# eib-64.net
KiCad netlist of a schematic drawn in EAGLE
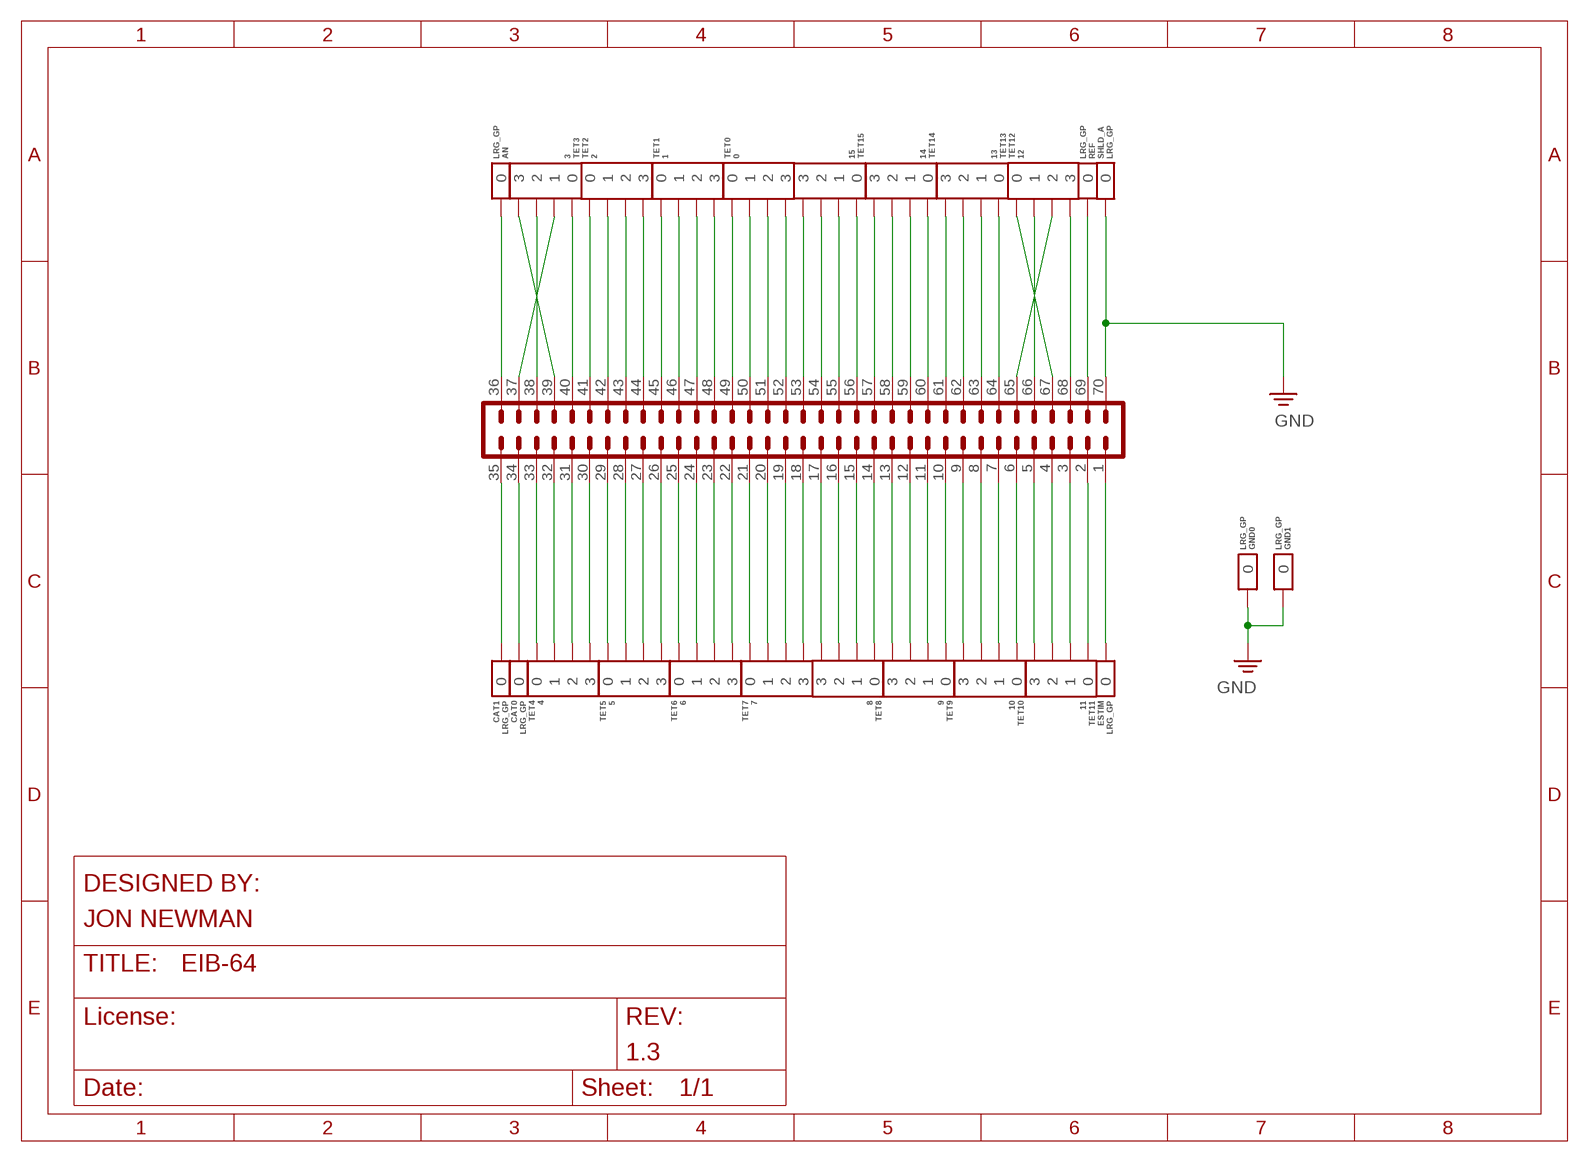
[diagram p0: schematic, sheet 1]

(export (version "E")
  (design (tool "Eeschema 10.0.6"))
  (components
    (comp (ref "AN")
      (value "LRG_GP")
      (footprint "eagle-import:GOLDPIN_0.5ID_0.7OD")
      (libsource (lib "eagle-import") (part "GOLDPIN_0.5ID_0.7OD"))
    )
    (comp (ref "CAT0")
      (value "LRG_GP")
      (footprint "eagle-import:GOLDPIN_0.5ID_0.7OD")
      (libsource (lib "eagle-import") (part "GOLDPIN_0.5ID_0.7OD"))
    )
    (comp (ref "CAT1")
      (value "LRG_GP")
      (footprint "eagle-import:GOLDPIN_0.5ID_0.7OD")
      (libsource (lib "eagle-import") (part "GOLDPIN_0.5ID_0.7OD"))
    )
    (comp (ref "ESTIM")
      (value "LRG_GP")
      (footprint "eagle-import:GOLDPIN_0.5ID_0.7OD")
      (libsource (lib "eagle-import") (part "GOLDPIN_0.5ID_0.7OD"))
    )
    (comp (ref "GND0")
      (value "LRG_GP")
      (footprint "eagle-import:GOLDPIN_0.5ID_0.7OD")
      (libsource (lib "eagle-import") (part "GOLDPIN_0.5ID_0.7OD"))
    )
    (comp (ref "GND1")
      (value "LRG_GP")
      (footprint "eagle-import:GOLDPIN_0.5ID_0.7OD")
      (libsource (lib "eagle-import") (part "GOLDPIN_0.5ID_0.7OD"))
    )
    (comp (ref "J1")
      (value "DF40-REC")
      (footprint "eagle-import:DF40-70REC")
      (libsource (lib "eagle-import") (part "PINHD-2X35_DF40REC"))
    )
    (comp (ref "REF")
      (value "LRG_GP")
      (footprint "eagle-import:GOLDPIN_0.5ID_0.7OD")
      (libsource (lib "eagle-import") (part "GOLDPIN_0.5ID_0.7OD"))
    )
    (comp (ref "SHLD_A")
      (value "LRG_GP")
      (footprint "eagle-import:GOLDPIN_0.5ID_0.7OD")
      (libsource (lib "eagle-import") (part "GOLDPIN_0.5ID_0.7OD"))
    )
    (comp (ref "TET0")
      (value "0")
      (footprint "eagle-import:TETRODE_0.3ID_LINEAR_MOUSE")
      (libsource (lib "eagle-import") (part "TETRODE_0.3ID_LINEAR_MOUSE"))
    )
    (comp (ref "TET1")
      (value "1")
      (footprint "eagle-import:TETRODE_0.3ID_LINEAR_MOUSE")
      (libsource (lib "eagle-import") (part "TETRODE_0.3ID_LINEAR_MOUSE"))
    )
    (comp (ref "TET2")
      (value "2")
      (footprint "eagle-import:TETRODE_0.3ID_LINEAR_MOUSE")
      (libsource (lib "eagle-import") (part "TETRODE_0.3ID_LINEAR_MOUSE"))
    )
    (comp (ref "TET3")
      (value "3")
      (footprint "eagle-import:TETRODE_0.3ID_LINEAR_MOUSE")
      (libsource (lib "eagle-import") (part "TETRODE_0.3ID_LINEAR_MOUSE"))
    )
    (comp (ref "TET4")
      (value "4")
      (footprint "eagle-import:TETRODE_0.3ID_LINEAR_MOUSE")
      (libsource (lib "eagle-import") (part "TETRODE_0.3ID_LINEAR_MOUSE"))
    )
    (comp (ref "TET5")
      (value "5")
      (footprint "eagle-import:TETRODE_0.3ID_LINEAR_MOUSE")
      (libsource (lib "eagle-import") (part "TETRODE_0.3ID_LINEAR_MOUSE"))
    )
    (comp (ref "TET6")
      (value "6")
      (footprint "eagle-import:TETRODE_0.3ID_LINEAR_MOUSE")
      (libsource (lib "eagle-import") (part "TETRODE_0.3ID_LINEAR_MOUSE"))
    )
    (comp (ref "TET7")
      (value "7")
      (footprint "eagle-import:TETRODE_0.3ID_LINEAR_MOUSE")
      (libsource (lib "eagle-import") (part "TETRODE_0.3ID_LINEAR_MOUSE"))
    )
    (comp (ref "TET8")
      (value "8")
      (footprint "eagle-import:TETRODE_0.3ID_LINEAR_MOUSE")
      (libsource (lib "eagle-import") (part "TETRODE_0.3ID_LINEAR_MOUSE"))
    )
    (comp (ref "TET9")
      (value "9")
      (footprint "eagle-import:TETRODE_0.3ID_LINEAR_MOUSE")
      (libsource (lib "eagle-import") (part "TETRODE_0.3ID_LINEAR_MOUSE"))
    )
    (comp (ref "TET10")
      (value "10")
      (footprint "eagle-import:TETRODE_0.3ID_LINEAR_MOUSE")
      (libsource (lib "eagle-import") (part "TETRODE_0.3ID_LINEAR_MOUSE"))
    )
    (comp (ref "TET11")
      (value "11")
      (footprint "eagle-import:TETRODE_0.3ID_LINEAR_MOUSE")
      (libsource (lib "eagle-import") (part "TETRODE_0.3ID_LINEAR_MOUSE"))
    )
    (comp (ref "TET12")
      (value "12")
      (footprint "eagle-import:TETRODE_0.3ID_LINEAR_MOUSE")
      (libsource (lib "eagle-import") (part "TETRODE_0.3ID_LINEAR_MOUSE"))
    )
    (comp (ref "TET13")
      (value "13")
      (footprint "eagle-import:TETRODE_0.3ID_LINEAR_MOUSE")
      (libsource (lib "eagle-import") (part "TETRODE_0.3ID_LINEAR_MOUSE"))
    )
    (comp (ref "TET14")
      (value "14")
      (footprint "eagle-import:TETRODE_0.3ID_LINEAR_MOUSE")
      (libsource (lib "eagle-import") (part "TETRODE_0.3ID_LINEAR_MOUSE"))
    )
    (comp (ref "TET15")
      (value "15")
      (footprint "eagle-import:TETRODE_0.3ID_LINEAR_MOUSE")
      (libsource (lib "eagle-import") (part "TETRODE_0.3ID_LINEAR_MOUSE"))
    )
  )
  (nets
    (net (code "1") (name "GND") (class "Default")
      (node (ref "GND0") (pin "P$1") (pinfunction "0_P$1") (pintype "bidirectional"))
      (node (ref "GND1") (pin "P$1") (pinfunction "0_P$1") (pintype "bidirectional"))
      (node (ref "J1") (pin "70") (pinfunction "70_70") (pintype "bidirectional"))
      (node (ref "SHLD_A") (pin "P$1") (pinfunction "0_P$1") (pintype "bidirectional"))
    )
    (net (code "2") (name "Net-(AN-0)") (class "Default")
      (node (ref "AN") (pin "P$1") (pinfunction "0_P$1") (pintype "bidirectional"))
      (node (ref "J1") (pin "36") (pinfunction "36_36") (pintype "bidirectional"))
    )
    (net (code "3") (name "Net-(CAT0-0)") (class "Default")
      (node (ref "CAT0") (pin "P$1") (pinfunction "0_P$1") (pintype "bidirectional"))
      (node (ref "J1") (pin "34") (pinfunction "34_34") (pintype "bidirectional"))
    )
    (net (code "4") (name "Net-(CAT1-0)") (class "Default")
      (node (ref "CAT1") (pin "P$1") (pinfunction "0_P$1") (pintype "bidirectional"))
      (node (ref "J1") (pin "35") (pinfunction "35_35") (pintype "bidirectional"))
    )
    (net (code "5") (name "Net-(ESTIM-0)") (class "Default")
      (node (ref "ESTIM") (pin "P$1") (pinfunction "0_P$1") (pintype "bidirectional"))
      (node (ref "J1") (pin "1") (pinfunction "1_1") (pintype "bidirectional"))
    )
    (net (code "6") (name "Net-(J1-Pad2)") (class "Default")
      (node (ref "J1") (pin "2") (pinfunction "2_2") (pintype "bidirectional"))
      (node (ref "TET11") (pin "0") (pinfunction "0_0") (pintype "bidirectional"))
    )
    (net (code "7") (name "Net-(J1-Pad3)") (class "Default")
      (node (ref "J1") (pin "3") (pinfunction "3_3") (pintype "bidirectional"))
      (node (ref "TET11") (pin "1") (pinfunction "1_1") (pintype "bidirectional"))
    )
    (net (code "8") (name "Net-(J1-Pad4)") (class "Default")
      (node (ref "J1") (pin "4") (pinfunction "4_4") (pintype "bidirectional"))
      (node (ref "TET11") (pin "2") (pinfunction "2_2") (pintype "bidirectional"))
    )
    (net (code "9") (name "Net-(J1-Pad5)") (class "Default")
      (node (ref "J1") (pin "5") (pinfunction "5_5") (pintype "bidirectional"))
      (node (ref "TET11") (pin "3") (pinfunction "3_3") (pintype "bidirectional"))
    )
    (net (code "10") (name "Net-(J1-Pad6)") (class "Default")
      (node (ref "J1") (pin "6") (pinfunction "6_6") (pintype "bidirectional"))
      (node (ref "TET10") (pin "0") (pinfunction "0_0") (pintype "bidirectional"))
    )
    (net (code "11") (name "Net-(J1-Pad7)") (class "Default")
      (node (ref "J1") (pin "7") (pinfunction "7_7") (pintype "bidirectional"))
      (node (ref "TET10") (pin "1") (pinfunction "1_1") (pintype "bidirectional"))
    )
    (net (code "12") (name "Net-(J1-Pad8)") (class "Default")
      (node (ref "J1") (pin "8") (pinfunction "8_8") (pintype "bidirectional"))
      (node (ref "TET10") (pin "2") (pinfunction "2_2") (pintype "bidirectional"))
    )
    (net (code "13") (name "Net-(J1-Pad9)") (class "Default")
      (node (ref "J1") (pin "9") (pinfunction "9_9") (pintype "bidirectional"))
      (node (ref "TET10") (pin "3") (pinfunction "3_3") (pintype "bidirectional"))
    )
    (net (code "14") (name "Net-(J1-Pad10)") (class "Default")
      (node (ref "J1") (pin "10") (pinfunction "10_10") (pintype "bidirectional"))
      (node (ref "TET9") (pin "0") (pinfunction "0_0") (pintype "bidirectional"))
    )
    (net (code "15") (name "Net-(J1-Pad11)") (class "Default")
      (node (ref "J1") (pin "11") (pinfunction "11_11") (pintype "bidirectional"))
      (node (ref "TET9") (pin "1") (pinfunction "1_1") (pintype "bidirectional"))
    )
    (net (code "16") (name "Net-(J1-Pad12)") (class "Default")
      (node (ref "J1") (pin "12") (pinfunction "12_12") (pintype "bidirectional"))
      (node (ref "TET9") (pin "2") (pinfunction "2_2") (pintype "bidirectional"))
    )
    (net (code "17") (name "Net-(J1-Pad13)") (class "Default")
      (node (ref "J1") (pin "13") (pinfunction "13_13") (pintype "bidirectional"))
      (node (ref "TET9") (pin "3") (pinfunction "3_3") (pintype "bidirectional"))
    )
    (net (code "18") (name "Net-(J1-Pad14)") (class "Default")
      (node (ref "J1") (pin "14") (pinfunction "14_14") (pintype "bidirectional"))
      (node (ref "TET8") (pin "0") (pinfunction "0_0") (pintype "bidirectional"))
    )
    (net (code "19") (name "Net-(J1-Pad15)") (class "Default")
      (node (ref "J1") (pin "15") (pinfunction "15_15") (pintype "bidirectional"))
      (node (ref "TET8") (pin "1") (pinfunction "1_1") (pintype "bidirectional"))
    )
    (net (code "20") (name "Net-(J1-Pad16)") (class "Default")
      (node (ref "J1") (pin "16") (pinfunction "16_16") (pintype "bidirectional"))
      (node (ref "TET8") (pin "2") (pinfunction "2_2") (pintype "bidirectional"))
    )
    (net (code "21") (name "Net-(J1-Pad17)") (class "Default")
      (node (ref "J1") (pin "17") (pinfunction "17_17") (pintype "bidirectional"))
      (node (ref "TET8") (pin "3") (pinfunction "3_3") (pintype "bidirectional"))
    )
    (net (code "22") (name "Net-(J1-Pad18)") (class "Default")
      (node (ref "J1") (pin "18") (pinfunction "18_18") (pintype "bidirectional"))
      (node (ref "TET7") (pin "3") (pinfunction "3_3") (pintype "bidirectional"))
    )
    (net (code "23") (name "Net-(J1-Pad19)") (class "Default")
      (node (ref "J1") (pin "19") (pinfunction "19_19") (pintype "bidirectional"))
      (node (ref "TET7") (pin "2") (pinfunction "2_2") (pintype "bidirectional"))
    )
    (net (code "24") (name "Net-(J1-Pad20)") (class "Default")
      (node (ref "J1") (pin "20") (pinfunction "20_20") (pintype "bidirectional"))
      (node (ref "TET7") (pin "1") (pinfunction "1_1") (pintype "bidirectional"))
    )
    (net (code "25") (name "Net-(J1-Pad21)") (class "Default")
      (node (ref "J1") (pin "21") (pinfunction "21_21") (pintype "bidirectional"))
      (node (ref "TET7") (pin "0") (pinfunction "0_0") (pintype "bidirectional"))
    )
    (net (code "26") (name "Net-(J1-Pad22)") (class "Default")
      (node (ref "J1") (pin "22") (pinfunction "22_22") (pintype "bidirectional"))
      (node (ref "TET6") (pin "3") (pinfunction "3_3") (pintype "bidirectional"))
    )
    (net (code "27") (name "Net-(J1-Pad23)") (class "Default")
      (node (ref "J1") (pin "23") (pinfunction "23_23") (pintype "bidirectional"))
      (node (ref "TET6") (pin "2") (pinfunction "2_2") (pintype "bidirectional"))
    )
    (net (code "28") (name "Net-(J1-Pad24)") (class "Default")
      (node (ref "J1") (pin "24") (pinfunction "24_24") (pintype "bidirectional"))
      (node (ref "TET6") (pin "1") (pinfunction "1_1") (pintype "bidirectional"))
    )
    (net (code "29") (name "Net-(J1-Pad25)") (class "Default")
      (node (ref "J1") (pin "25") (pinfunction "25_25") (pintype "bidirectional"))
      (node (ref "TET6") (pin "0") (pinfunction "0_0") (pintype "bidirectional"))
    )
    (net (code "30") (name "Net-(J1-Pad26)") (class "Default")
      (node (ref "J1") (pin "26") (pinfunction "26_26") (pintype "bidirectional"))
      (node (ref "TET5") (pin "3") (pinfunction "3_3") (pintype "bidirectional"))
    )
    (net (code "31") (name "Net-(J1-Pad27)") (class "Default")
      (node (ref "J1") (pin "27") (pinfunction "27_27") (pintype "bidirectional"))
      (node (ref "TET5") (pin "2") (pinfunction "2_2") (pintype "bidirectional"))
    )
    (net (code "32") (name "Net-(J1-Pad28)") (class "Default")
      (node (ref "J1") (pin "28") (pinfunction "28_28") (pintype "bidirectional"))
      (node (ref "TET5") (pin "1") (pinfunction "1_1") (pintype "bidirectional"))
    )
    (net (code "33") (name "Net-(J1-Pad29)") (class "Default")
      (node (ref "J1") (pin "29") (pinfunction "29_29") (pintype "bidirectional"))
      (node (ref "TET5") (pin "0") (pinfunction "0_0") (pintype "bidirectional"))
    )
    (net (code "34") (name "Net-(J1-Pad30)") (class "Default")
      (node (ref "J1") (pin "30") (pinfunction "30_30") (pintype "bidirectional"))
      (node (ref "TET4") (pin "3") (pinfunction "3_3") (pintype "bidirectional"))
    )
    (net (code "35") (name "Net-(J1-Pad31)") (class "Default")
      (node (ref "J1") (pin "31") (pinfunction "31_31") (pintype "bidirectional"))
      (node (ref "TET4") (pin "2") (pinfunction "2_2") (pintype "bidirectional"))
    )
    (net (code "36") (name "Net-(J1-Pad32)") (class "Default")
      (node (ref "J1") (pin "32") (pinfunction "32_32") (pintype "bidirectional"))
      (node (ref "TET4") (pin "1") (pinfunction "1_1") (pintype "bidirectional"))
    )
    (net (code "37") (name "Net-(J1-Pad33)") (class "Default")
      (node (ref "J1") (pin "33") (pinfunction "33_33") (pintype "bidirectional"))
      (node (ref "TET4") (pin "0") (pinfunction "0_0") (pintype "bidirectional"))
    )
    (net (code "38") (name "Net-(J1-Pad37)") (class "Default")
      (node (ref "J1") (pin "37") (pinfunction "37_37") (pintype "bidirectional"))
      (node (ref "TET3") (pin "1") (pinfunction "1_1") (pintype "bidirectional"))
    )
    (net (code "39") (name "Net-(J1-Pad38)") (class "Default")
      (node (ref "J1") (pin "38") (pinfunction "38_38") (pintype "bidirectional"))
      (node (ref "TET3") (pin "2") (pinfunction "2_2") (pintype "bidirectional"))
    )
    (net (code "40") (name "Net-(J1-Pad39)") (class "Default")
      (node (ref "J1") (pin "39") (pinfunction "39_39") (pintype "bidirectional"))
      (node (ref "TET3") (pin "3") (pinfunction "3_3") (pintype "bidirectional"))
    )
    (net (code "41") (name "Net-(J1-Pad40)") (class "Default")
      (node (ref "J1") (pin "40") (pinfunction "40_40") (pintype "bidirectional"))
      (node (ref "TET3") (pin "0") (pinfunction "0_0") (pintype "bidirectional"))
    )
    (net (code "42") (name "Net-(J1-Pad41)") (class "Default")
      (node (ref "J1") (pin "41") (pinfunction "41_41") (pintype "bidirectional"))
      (node (ref "TET2") (pin "0") (pinfunction "0_0") (pintype "bidirectional"))
    )
    (net (code "43") (name "Net-(J1-Pad42)") (class "Default")
      (node (ref "J1") (pin "42") (pinfunction "42_42") (pintype "bidirectional"))
      (node (ref "TET2") (pin "1") (pinfunction "1_1") (pintype "bidirectional"))
    )
    (net (code "44") (name "Net-(J1-Pad43)") (class "Default")
      (node (ref "J1") (pin "43") (pinfunction "43_43") (pintype "bidirectional"))
      (node (ref "TET2") (pin "2") (pinfunction "2_2") (pintype "bidirectional"))
    )
    (net (code "45") (name "Net-(J1-Pad44)") (class "Default")
      (node (ref "J1") (pin "44") (pinfunction "44_44") (pintype "bidirectional"))
      (node (ref "TET2") (pin "3") (pinfunction "3_3") (pintype "bidirectional"))
    )
    (net (code "46") (name "Net-(J1-Pad45)") (class "Default")
      (node (ref "J1") (pin "45") (pinfunction "45_45") (pintype "bidirectional"))
      (node (ref "TET1") (pin "0") (pinfunction "0_0") (pintype "bidirectional"))
    )
    (net (code "47") (name "Net-(J1-Pad46)") (class "Default")
      (node (ref "J1") (pin "46") (pinfunction "46_46") (pintype "bidirectional"))
      (node (ref "TET1") (pin "1") (pinfunction "1_1") (pintype "bidirectional"))
    )
    (net (code "48") (name "Net-(J1-Pad47)") (class "Default")
      (node (ref "J1") (pin "47") (pinfunction "47_47") (pintype "bidirectional"))
      (node (ref "TET1") (pin "2") (pinfunction "2_2") (pintype "bidirectional"))
    )
    (net (code "49") (name "Net-(J1-Pad48)") (class "Default")
      (node (ref "J1") (pin "48") (pinfunction "48_48") (pintype "bidirectional"))
      (node (ref "TET1") (pin "3") (pinfunction "3_3") (pintype "bidirectional"))
    )
    (net (code "50") (name "Net-(J1-Pad49)") (class "Default")
      (node (ref "J1") (pin "49") (pinfunction "49_49") (pintype "bidirectional"))
      (node (ref "TET0") (pin "0") (pinfunction "0_0") (pintype "bidirectional"))
    )
    (net (code "51") (name "Net-(J1-Pad50)") (class "Default")
      (node (ref "J1") (pin "50") (pinfunction "50_50") (pintype "bidirectional"))
      (node (ref "TET0") (pin "1") (pinfunction "1_1") (pintype "bidirectional"))
    )
    (net (code "52") (name "Net-(J1-Pad51)") (class "Default")
      (node (ref "J1") (pin "51") (pinfunction "51_51") (pintype "bidirectional"))
      (node (ref "TET0") (pin "2") (pinfunction "2_2") (pintype "bidirectional"))
    )
    (net (code "53") (name "Net-(J1-Pad52)") (class "Default")
      (node (ref "J1") (pin "52") (pinfunction "52_52") (pintype "bidirectional"))
      (node (ref "TET0") (pin "3") (pinfunction "3_3") (pintype "bidirectional"))
    )
    (net (code "54") (name "Net-(J1-Pad53)") (class "Default")
      (node (ref "J1") (pin "53") (pinfunction "53_53") (pintype "bidirectional"))
      (node (ref "TET15") (pin "3") (pinfunction "3_3") (pintype "bidirectional"))
    )
    (net (code "55") (name "Net-(J1-Pad54)") (class "Default")
      (node (ref "J1") (pin "54") (pinfunction "54_54") (pintype "bidirectional"))
      (node (ref "TET15") (pin "2") (pinfunction "2_2") (pintype "bidirectional"))
    )
    (net (code "56") (name "Net-(J1-Pad55)") (class "Default")
      (node (ref "J1") (pin "55") (pinfunction "55_55") (pintype "bidirectional"))
      (node (ref "TET15") (pin "1") (pinfunction "1_1") (pintype "bidirectional"))
    )
    (net (code "57") (name "Net-(J1-Pad56)") (class "Default")
      (node (ref "J1") (pin "56") (pinfunction "56_56") (pintype "bidirectional"))
      (node (ref "TET15") (pin "0") (pinfunction "0_0") (pintype "bidirectional"))
    )
    (net (code "58") (name "Net-(J1-Pad57)") (class "Default")
      (node (ref "J1") (pin "57") (pinfunction "57_57") (pintype "bidirectional"))
      (node (ref "TET14") (pin "3") (pinfunction "3_3") (pintype "bidirectional"))
    )
    (net (code "59") (name "Net-(J1-Pad58)") (class "Default")
      (node (ref "J1") (pin "58") (pinfunction "58_58") (pintype "bidirectional"))
      (node (ref "TET14") (pin "2") (pinfunction "2_2") (pintype "bidirectional"))
    )
    (net (code "60") (name "Net-(J1-Pad59)") (class "Default")
      (node (ref "J1") (pin "59") (pinfunction "59_59") (pintype "bidirectional"))
      (node (ref "TET14") (pin "1") (pinfunction "1_1") (pintype "bidirectional"))
    )
    (net (code "61") (name "Net-(J1-Pad60)") (class "Default")
      (node (ref "J1") (pin "60") (pinfunction "60_60") (pintype "bidirectional"))
      (node (ref "TET14") (pin "0") (pinfunction "0_0") (pintype "bidirectional"))
    )
    (net (code "62") (name "Net-(J1-Pad61)") (class "Default")
      (node (ref "J1") (pin "61") (pinfunction "61_61") (pintype "bidirectional"))
      (node (ref "TET13") (pin "3") (pinfunction "3_3") (pintype "bidirectional"))
    )
    (net (code "63") (name "Net-(J1-Pad62)") (class "Default")
      (node (ref "J1") (pin "62") (pinfunction "62_62") (pintype "bidirectional"))
      (node (ref "TET13") (pin "2") (pinfunction "2_2") (pintype "bidirectional"))
    )
    (net (code "64") (name "Net-(J1-Pad63)") (class "Default")
      (node (ref "J1") (pin "63") (pinfunction "63_63") (pintype "bidirectional"))
      (node (ref "TET13") (pin "1") (pinfunction "1_1") (pintype "bidirectional"))
    )
    (net (code "65") (name "Net-(J1-Pad64)") (class "Default")
      (node (ref "J1") (pin "64") (pinfunction "64_64") (pintype "bidirectional"))
      (node (ref "TET13") (pin "0") (pinfunction "0_0") (pintype "bidirectional"))
    )
    (net (code "66") (name "Net-(J1-Pad65)") (class "Default")
      (node (ref "J1") (pin "65") (pinfunction "65_65") (pintype "bidirectional"))
      (node (ref "TET12") (pin "2") (pinfunction "2_2") (pintype "bidirectional"))
    )
    (net (code "67") (name "Net-(J1-Pad66)") (class "Default")
      (node (ref "J1") (pin "66") (pinfunction "66_66") (pintype "bidirectional"))
      (node (ref "TET12") (pin "1") (pinfunction "1_1") (pintype "bidirectional"))
    )
    (net (code "68") (name "Net-(J1-Pad67)") (class "Default")
      (node (ref "J1") (pin "67") (pinfunction "67_67") (pintype "bidirectional"))
      (node (ref "TET12") (pin "0") (pinfunction "0_0") (pintype "bidirectional"))
    )
    (net (code "69") (name "Net-(J1-Pad68)") (class "Default")
      (node (ref "J1") (pin "68") (pinfunction "68_68") (pintype "bidirectional"))
      (node (ref "TET12") (pin "3") (pinfunction "3_3") (pintype "bidirectional"))
    )
    (net (code "70") (name "Net-(REF-0)") (class "Default")
      (node (ref "J1") (pin "69") (pinfunction "69_69") (pintype "bidirectional"))
      (node (ref "REF") (pin "P$1") (pinfunction "0_P$1") (pintype "bidirectional"))
    )
  )
)
